# lixie_digit.net
KiCad netlist of a schematic drawn in EAGLE
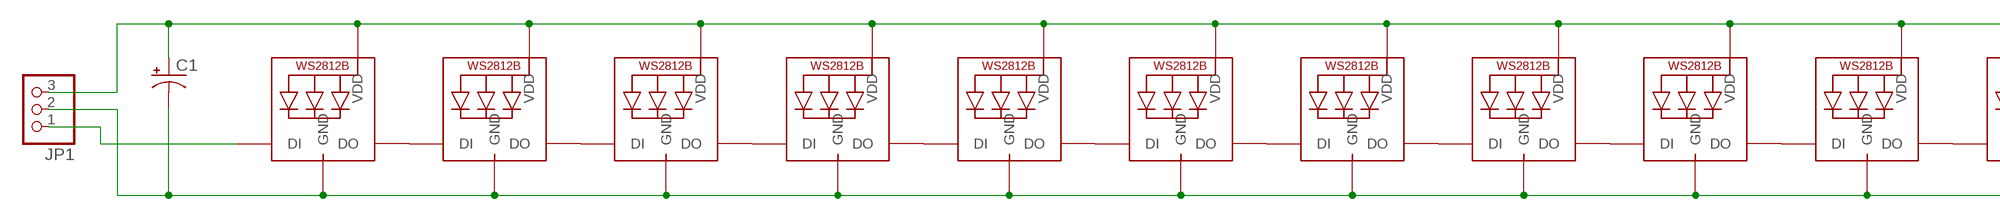
[diagram p0: schematic, sheet 1, part 1 of 2]
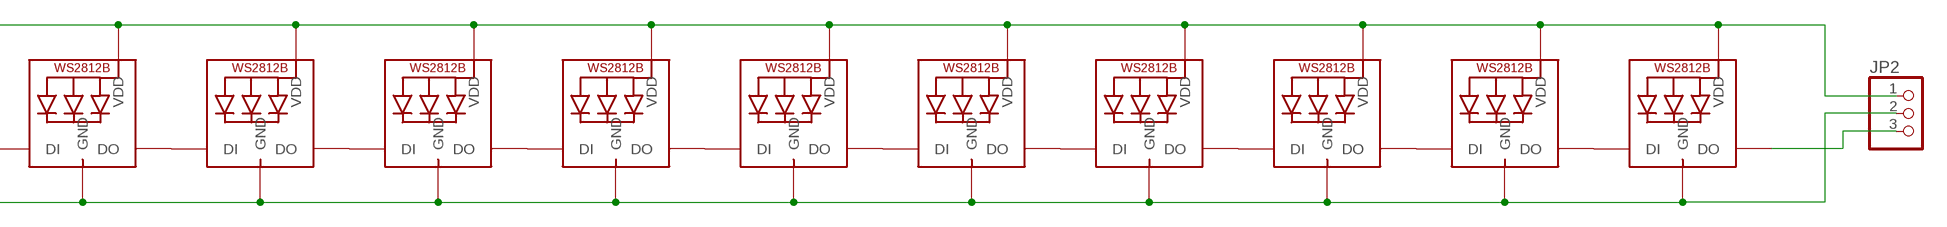
[diagram p1: schematic, sheet 1, part 2 of 2]

(export (version "E")
  (design (tool "Eeschema 10.0.6"))
  (components
    (comp (ref "C1")
      (value "CPOL-USE3.5-8")
      (footprint "eagle-import:E3,5-8")
      (libsource (lib "eagle-import") (part "CPOL-USE3.5-8"))
    )
    (comp (ref "JP1")
      (value "PINHD-1X3")
      (footprint "eagle-import:1X03")
      (libsource (lib "eagle-import") (part "PINHD-1X3"))
    )
    (comp (ref "JP2")
      (value "PINHD-1X3")
      (footprint "eagle-import:1X03")
      (libsource (lib "eagle-import") (part "PINHD-1X3"))
    )
    (comp (ref "LED1")
      (value "WS2812B5050")
      (footprint "eagle-import:WS2812B")
      (libsource (lib "eagle-import") (part "WS2812B5050"))
    )
    (comp (ref "LED2")
      (value "WS2812B5050")
      (footprint "eagle-import:WS2812B")
      (libsource (lib "eagle-import") (part "WS2812B5050"))
    )
    (comp (ref "LED3")
      (value "WS2812B5050")
      (footprint "eagle-import:WS2812B")
      (libsource (lib "eagle-import") (part "WS2812B5050"))
    )
    (comp (ref "LED4")
      (value "WS2812B5050")
      (footprint "eagle-import:WS2812B")
      (libsource (lib "eagle-import") (part "WS2812B5050"))
    )
    (comp (ref "LED5")
      (value "WS2812B5050")
      (footprint "eagle-import:WS2812B")
      (libsource (lib "eagle-import") (part "WS2812B5050"))
    )
    (comp (ref "LED6")
      (value "WS2812B5050")
      (footprint "eagle-import:WS2812B")
      (libsource (lib "eagle-import") (part "WS2812B5050"))
    )
    (comp (ref "LED7")
      (value "WS2812B5050")
      (footprint "eagle-import:WS2812B")
      (libsource (lib "eagle-import") (part "WS2812B5050"))
    )
    (comp (ref "LED8")
      (value "WS2812B5050")
      (footprint "eagle-import:WS2812B")
      (libsource (lib "eagle-import") (part "WS2812B5050"))
    )
    (comp (ref "LED9")
      (value "WS2812B5050")
      (footprint "eagle-import:WS2812B")
      (libsource (lib "eagle-import") (part "WS2812B5050"))
    )
    (comp (ref "LED10")
      (value "WS2812B5050")
      (footprint "eagle-import:WS2812B")
      (libsource (lib "eagle-import") (part "WS2812B5050"))
    )
    (comp (ref "LED11")
      (value "WS2812B5050")
      (footprint "eagle-import:WS2812B")
      (libsource (lib "eagle-import") (part "WS2812B5050"))
    )
    (comp (ref "LED12")
      (value "WS2812B5050")
      (footprint "eagle-import:WS2812B")
      (libsource (lib "eagle-import") (part "WS2812B5050"))
    )
    (comp (ref "LED13")
      (value "WS2812B5050")
      (footprint "eagle-import:WS2812B")
      (libsource (lib "eagle-import") (part "WS2812B5050"))
    )
    (comp (ref "LED14")
      (value "WS2812B5050")
      (footprint "eagle-import:WS2812B")
      (libsource (lib "eagle-import") (part "WS2812B5050"))
    )
    (comp (ref "LED15")
      (value "WS2812B5050")
      (footprint "eagle-import:WS2812B")
      (libsource (lib "eagle-import") (part "WS2812B5050"))
    )
    (comp (ref "LED16")
      (value "WS2812B5050")
      (footprint "eagle-import:WS2812B")
      (libsource (lib "eagle-import") (part "WS2812B5050"))
    )
    (comp (ref "LED17")
      (value "WS2812B5050")
      (footprint "eagle-import:WS2812B")
      (libsource (lib "eagle-import") (part "WS2812B5050"))
    )
    (comp (ref "LED18")
      (value "WS2812B5050")
      (footprint "eagle-import:WS2812B")
      (libsource (lib "eagle-import") (part "WS2812B5050"))
    )
    (comp (ref "LED19")
      (value "WS2812B5050")
      (footprint "eagle-import:WS2812B")
      (libsource (lib "eagle-import") (part "WS2812B5050"))
    )
    (comp (ref "LED20")
      (value "WS2812B5050")
      (footprint "eagle-import:WS2812B")
      (libsource (lib "eagle-import") (part "WS2812B5050"))
    )
  )
  (nets
    (net (code "1") (name "Net-(LED1-DI)") (class "Default")
      (node (ref "JP1") (pin "1") (pinfunction "1_1") (pintype "passive"))
      (node (ref "LED1") (pin "4-DIN") (pinfunction "DI_4-DIN") (pintype "input"))
    )
    (net (code "2") (name "Net-(LED1-DO)") (class "Default")
      (node (ref "LED1") (pin "2-DOUT") (pinfunction "DO_2-DOUT") (pintype "output"))
      (node (ref "LED2") (pin "4-DIN") (pinfunction "DI_4-DIN") (pintype "input"))
    )
    (net (code "3") (name "Net-(LED1-GND)") (class "Default")
      (node (ref "C1") (pin "-") (pinfunction "-_-") (pintype "passive"))
      (node (ref "JP1") (pin "2") (pinfunction "2_2") (pintype "passive"))
      (node (ref "JP2") (pin "2") (pinfunction "2_2") (pintype "passive"))
      (node (ref "LED1") (pin "3-GND") (pinfunction "GND_3-GND") (pintype "power_in"))
      (node (ref "LED10") (pin "3-GND") (pinfunction "GND_3-GND") (pintype "power_in"))
      (node (ref "LED11") (pin "3-GND") (pinfunction "GND_3-GND") (pintype "power_in"))
      (node (ref "LED12") (pin "3-GND") (pinfunction "GND_3-GND") (pintype "power_in"))
      (node (ref "LED13") (pin "3-GND") (pinfunction "GND_3-GND") (pintype "power_in"))
      (node (ref "LED14") (pin "3-GND") (pinfunction "GND_3-GND") (pintype "power_in"))
      (node (ref "LED15") (pin "3-GND") (pinfunction "GND_3-GND") (pintype "power_in"))
      (node (ref "LED16") (pin "3-GND") (pinfunction "GND_3-GND") (pintype "power_in"))
      (node (ref "LED17") (pin "3-GND") (pinfunction "GND_3-GND") (pintype "power_in"))
      (node (ref "LED18") (pin "3-GND") (pinfunction "GND_3-GND") (pintype "power_in"))
      (node (ref "LED19") (pin "3-GND") (pinfunction "GND_3-GND") (pintype "power_in"))
      (node (ref "LED2") (pin "3-GND") (pinfunction "GND_3-GND") (pintype "power_in"))
      (node (ref "LED20") (pin "3-GND") (pinfunction "GND_3-GND") (pintype "power_in"))
      (node (ref "LED3") (pin "3-GND") (pinfunction "GND_3-GND") (pintype "power_in"))
      (node (ref "LED4") (pin "3-GND") (pinfunction "GND_3-GND") (pintype "power_in"))
      (node (ref "LED5") (pin "3-GND") (pinfunction "GND_3-GND") (pintype "power_in"))
      (node (ref "LED6") (pin "3-GND") (pinfunction "GND_3-GND") (pintype "power_in"))
      (node (ref "LED7") (pin "3-GND") (pinfunction "GND_3-GND") (pintype "power_in"))
      (node (ref "LED8") (pin "3-GND") (pinfunction "GND_3-GND") (pintype "power_in"))
      (node (ref "LED9") (pin "3-GND") (pinfunction "GND_3-GND") (pintype "power_in"))
    )
    (net (code "4") (name "Net-(LED1-VDD)") (class "Default")
      (node (ref "C1") (pin "+") (pinfunction "+_+") (pintype "passive"))
      (node (ref "JP1") (pin "3") (pinfunction "3_3") (pintype "passive"))
      (node (ref "JP2") (pin "1") (pinfunction "1_1") (pintype "passive"))
      (node (ref "LED1") (pin "1-VDD") (pinfunction "VDD_1-VDD") (pintype "power_in"))
      (node (ref "LED10") (pin "1-VDD") (pinfunction "VDD_1-VDD") (pintype "power_in"))
      (node (ref "LED11") (pin "1-VDD") (pinfunction "VDD_1-VDD") (pintype "power_in"))
      (node (ref "LED12") (pin "1-VDD") (pinfunction "VDD_1-VDD") (pintype "power_in"))
      (node (ref "LED13") (pin "1-VDD") (pinfunction "VDD_1-VDD") (pintype "power_in"))
      (node (ref "LED14") (pin "1-VDD") (pinfunction "VDD_1-VDD") (pintype "power_in"))
      (node (ref "LED15") (pin "1-VDD") (pinfunction "VDD_1-VDD") (pintype "power_in"))
      (node (ref "LED16") (pin "1-VDD") (pinfunction "VDD_1-VDD") (pintype "power_in"))
      (node (ref "LED17") (pin "1-VDD") (pinfunction "VDD_1-VDD") (pintype "power_in"))
      (node (ref "LED18") (pin "1-VDD") (pinfunction "VDD_1-VDD") (pintype "power_in"))
      (node (ref "LED19") (pin "1-VDD") (pinfunction "VDD_1-VDD") (pintype "power_in"))
      (node (ref "LED2") (pin "1-VDD") (pinfunction "VDD_1-VDD") (pintype "power_in"))
      (node (ref "LED20") (pin "1-VDD") (pinfunction "VDD_1-VDD") (pintype "power_in"))
      (node (ref "LED3") (pin "1-VDD") (pinfunction "VDD_1-VDD") (pintype "power_in"))
      (node (ref "LED4") (pin "1-VDD") (pinfunction "VDD_1-VDD") (pintype "power_in"))
      (node (ref "LED5") (pin "1-VDD") (pinfunction "VDD_1-VDD") (pintype "power_in"))
      (node (ref "LED6") (pin "1-VDD") (pinfunction "VDD_1-VDD") (pintype "power_in"))
      (node (ref "LED7") (pin "1-VDD") (pinfunction "VDD_1-VDD") (pintype "power_in"))
      (node (ref "LED8") (pin "1-VDD") (pinfunction "VDD_1-VDD") (pintype "power_in"))
      (node (ref "LED9") (pin "1-VDD") (pinfunction "VDD_1-VDD") (pintype "power_in"))
    )
    (net (code "5") (name "Net-(LED2-DO)") (class "Default")
      (node (ref "LED2") (pin "2-DOUT") (pinfunction "DO_2-DOUT") (pintype "output"))
      (node (ref "LED3") (pin "4-DIN") (pinfunction "DI_4-DIN") (pintype "input"))
    )
    (net (code "6") (name "Net-(LED3-DO)") (class "Default")
      (node (ref "LED3") (pin "2-DOUT") (pinfunction "DO_2-DOUT") (pintype "output"))
      (node (ref "LED4") (pin "4-DIN") (pinfunction "DI_4-DIN") (pintype "input"))
    )
    (net (code "7") (name "Net-(LED4-DO)") (class "Default")
      (node (ref "LED4") (pin "2-DOUT") (pinfunction "DO_2-DOUT") (pintype "output"))
      (node (ref "LED5") (pin "4-DIN") (pinfunction "DI_4-DIN") (pintype "input"))
    )
    (net (code "8") (name "Net-(LED5-DO)") (class "Default")
      (node (ref "LED5") (pin "2-DOUT") (pinfunction "DO_2-DOUT") (pintype "output"))
      (node (ref "LED6") (pin "4-DIN") (pinfunction "DI_4-DIN") (pintype "input"))
    )
    (net (code "9") (name "Net-(LED6-DO)") (class "Default")
      (node (ref "LED6") (pin "2-DOUT") (pinfunction "DO_2-DOUT") (pintype "output"))
      (node (ref "LED7") (pin "4-DIN") (pinfunction "DI_4-DIN") (pintype "input"))
    )
    (net (code "10") (name "Net-(LED7-DO)") (class "Default")
      (node (ref "LED7") (pin "2-DOUT") (pinfunction "DO_2-DOUT") (pintype "output"))
      (node (ref "LED8") (pin "4-DIN") (pinfunction "DI_4-DIN") (pintype "input"))
    )
    (net (code "11") (name "Net-(LED8-DO)") (class "Default")
      (node (ref "LED8") (pin "2-DOUT") (pinfunction "DO_2-DOUT") (pintype "output"))
      (node (ref "LED9") (pin "4-DIN") (pinfunction "DI_4-DIN") (pintype "input"))
    )
    (net (code "12") (name "Net-(LED10-DI)") (class "Default")
      (node (ref "LED10") (pin "4-DIN") (pinfunction "DI_4-DIN") (pintype "input"))
      (node (ref "LED9") (pin "2-DOUT") (pinfunction "DO_2-DOUT") (pintype "output"))
    )
    (net (code "13") (name "Net-(LED10-DO)") (class "Default")
      (node (ref "LED10") (pin "2-DOUT") (pinfunction "DO_2-DOUT") (pintype "output"))
      (node (ref "LED11") (pin "4-DIN") (pinfunction "DI_4-DIN") (pintype "input"))
    )
    (net (code "14") (name "Net-(LED11-DO)") (class "Default")
      (node (ref "LED11") (pin "2-DOUT") (pinfunction "DO_2-DOUT") (pintype "output"))
      (node (ref "LED12") (pin "4-DIN") (pinfunction "DI_4-DIN") (pintype "input"))
    )
    (net (code "15") (name "Net-(LED12-DO)") (class "Default")
      (node (ref "LED12") (pin "2-DOUT") (pinfunction "DO_2-DOUT") (pintype "output"))
      (node (ref "LED13") (pin "4-DIN") (pinfunction "DI_4-DIN") (pintype "input"))
    )
    (net (code "16") (name "Net-(LED13-DO)") (class "Default")
      (node (ref "LED13") (pin "2-DOUT") (pinfunction "DO_2-DOUT") (pintype "output"))
      (node (ref "LED14") (pin "4-DIN") (pinfunction "DI_4-DIN") (pintype "input"))
    )
    (net (code "17") (name "Net-(LED14-DO)") (class "Default")
      (node (ref "LED14") (pin "2-DOUT") (pinfunction "DO_2-DOUT") (pintype "output"))
      (node (ref "LED15") (pin "4-DIN") (pinfunction "DI_4-DIN") (pintype "input"))
    )
    (net (code "18") (name "Net-(LED15-DO)") (class "Default")
      (node (ref "LED15") (pin "2-DOUT") (pinfunction "DO_2-DOUT") (pintype "output"))
      (node (ref "LED16") (pin "4-DIN") (pinfunction "DI_4-DIN") (pintype "input"))
    )
    (net (code "19") (name "Net-(LED16-DO)") (class "Default")
      (node (ref "LED16") (pin "2-DOUT") (pinfunction "DO_2-DOUT") (pintype "output"))
      (node (ref "LED17") (pin "4-DIN") (pinfunction "DI_4-DIN") (pintype "input"))
    )
    (net (code "20") (name "Net-(LED17-DO)") (class "Default")
      (node (ref "LED17") (pin "2-DOUT") (pinfunction "DO_2-DOUT") (pintype "output"))
      (node (ref "LED18") (pin "4-DIN") (pinfunction "DI_4-DIN") (pintype "input"))
    )
    (net (code "21") (name "Net-(LED18-DO)") (class "Default")
      (node (ref "LED18") (pin "2-DOUT") (pinfunction "DO_2-DOUT") (pintype "output"))
      (node (ref "LED19") (pin "4-DIN") (pinfunction "DI_4-DIN") (pintype "input"))
    )
    (net (code "22") (name "Net-(LED19-DO)") (class "Default")
      (node (ref "LED19") (pin "2-DOUT") (pinfunction "DO_2-DOUT") (pintype "output"))
      (node (ref "LED20") (pin "4-DIN") (pinfunction "DI_4-DIN") (pintype "input"))
    )
    (net (code "23") (name "Net-(LED20-DO)") (class "Default")
      (node (ref "JP2") (pin "3") (pinfunction "3_3") (pintype "passive"))
      (node (ref "LED20") (pin "2-DOUT") (pinfunction "DO_2-DOUT") (pintype "output"))
    )
  )
)
